# 8_Front_Pannel_Con.net
KiCad netlist of a schematic drawn in Altium Designer
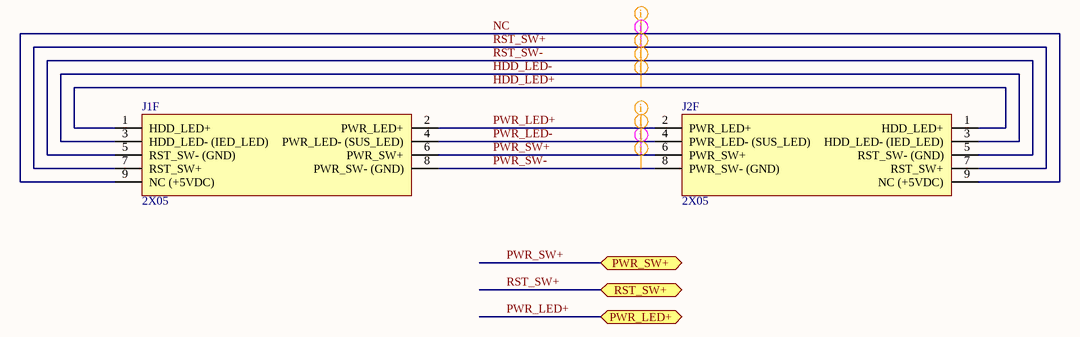
[diagram p0: 8_Front_Pannel_Con.SchDoc]

(export (version "E")
  (design (tool "Eeschema 10.0.6"))
  (components
    (comp (ref "J1F")
      (value "2X05")
      (footprint "Front_Pannel_2x05_P2.54mm_Horizontal_Right")
      (libsource (lib "") (part "Front_Pannel_2x05_P2.54mm_1"))
    )
    (comp (ref "J2F")
      (value "2X05")
      (footprint "Front_Pannel_2x05_P2.54mm_Horizontal_Left")
      (libsource (lib "Lib_Connector_PinHeader_2.54mm") (part "Front_Pannel_2x05_P2.54mm"))
    )
  )
  (nets
    (net (code "1") (name "/HDD_LED+") (class "Default")
      (node (ref "J1F") (pin "1") (pinfunction "HDD_LED+_1") (pintype "passive"))
      (node (ref "J2F") (pin "1") (pinfunction "HDD_LED+_1") (pintype "passive"))
    )
    (net (code "2") (name "/HDD_LED-") (class "Default")
      (node (ref "J1F") (pin "3") (pinfunction "HDD_LED-_(IED_LED)_3") (pintype "passive"))
      (node (ref "J2F") (pin "3") (pinfunction "HDD_LED-_(IED_LED)_3") (pintype "passive"))
    )
    (net (code "3") (name "/NC") (class "Default")
      (node (ref "J1F") (pin "9") (pinfunction "NC_(+5VDC)_9") (pintype "passive"))
      (node (ref "J2F") (pin "9") (pinfunction "NC_(+5VDC)_9") (pintype "passive"))
    )
    (net (code "4") (name "/PWR_LED+") (class "Default")
      (node (ref "J1F") (pin "2") (pinfunction "PWR_LED+_2") (pintype "passive"))
      (node (ref "J2F") (pin "2") (pinfunction "PWR_LED+_2") (pintype "passive"))
    )
    (net (code "5") (name "/PWR_LED-") (class "Default")
      (node (ref "J1F") (pin "4") (pinfunction "PWR_LED-_(SUS_LED)_4") (pintype "passive"))
      (node (ref "J2F") (pin "4") (pinfunction "PWR_LED-_(SUS_LED)_4") (pintype "passive"))
    )
    (net (code "6") (name "/PWR_SW+") (class "Default")
      (node (ref "J1F") (pin "6") (pinfunction "PWR_SW+_6") (pintype "passive"))
      (node (ref "J2F") (pin "6") (pinfunction "PWR_SW+_6") (pintype "passive"))
    )
    (net (code "7") (name "/PWR_SW-") (class "Default")
      (node (ref "J1F") (pin "8") (pinfunction "PWR_SW-_(GND)_8") (pintype "passive"))
      (node (ref "J2F") (pin "8") (pinfunction "PWR_SW-_(GND)_8") (pintype "passive"))
    )
    (net (code "8") (name "/RST_SW+") (class "Default")
      (node (ref "J1F") (pin "7") (pinfunction "RST_SW+_7") (pintype "passive"))
      (node (ref "J2F") (pin "7") (pinfunction "RST_SW+_7") (pintype "passive"))
    )
    (net (code "9") (name "/RST_SW-") (class "Default")
      (node (ref "J1F") (pin "5") (pinfunction "RST_SW-_(GND)_5") (pintype "passive"))
      (node (ref "J2F") (pin "5") (pinfunction "RST_SW-_(GND)_5") (pintype "passive"))
    )
  )
)
